# Sensore_esterno.net
KiCad netlist of a schematic drawn in EAGLE
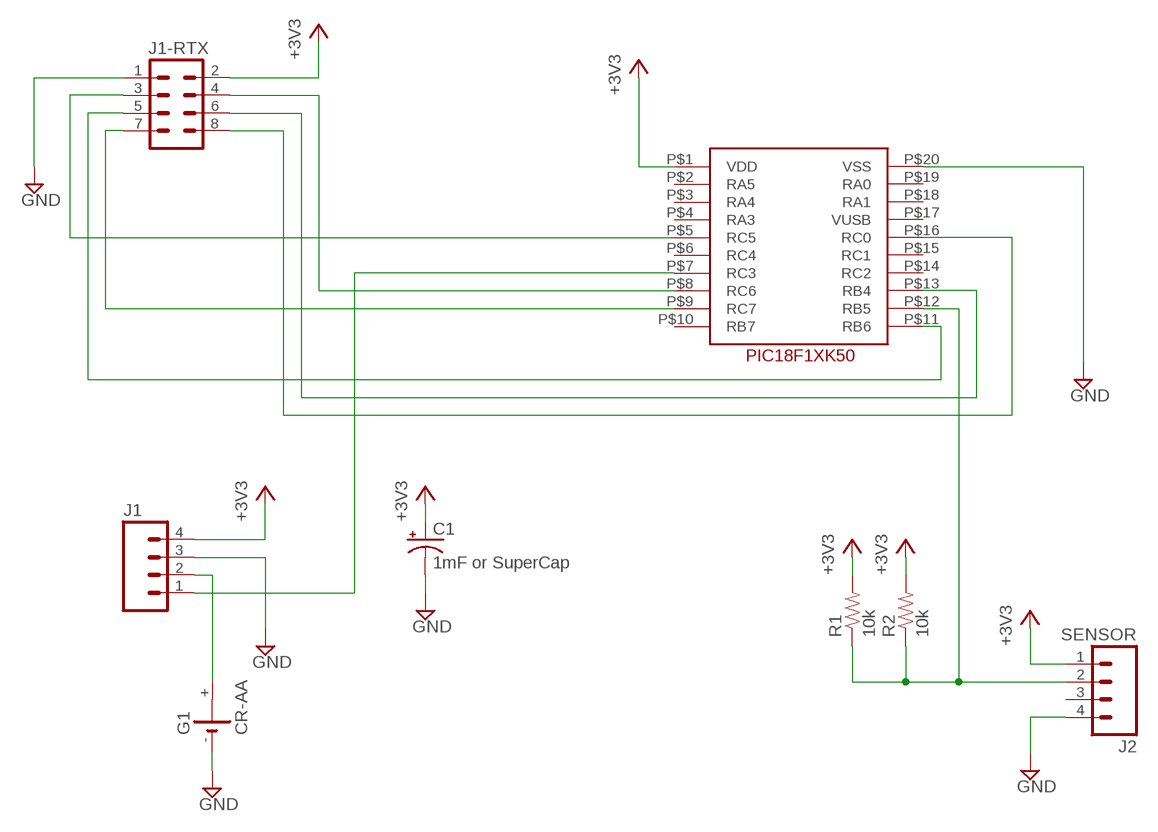
[diagram p0: schematic, sheet 1]

(export (version "E")
  (design (tool "Eeschema 10.0.6"))
  (components
    (comp (ref "C1")
      (value "1mF or SuperCap")
      (footprint "eagle-import:CPOL-RADIAL-1000UF-25V")
      (libsource (lib "eagle-import") (part "CAP_POLPTH4"))
    )
    (comp (ref "G1")
      (value "CR-AA")
      (footprint "eagle-import:CRAA")
      (libsource (lib "eagle-import") (part "CR-AA"))
    )
    (comp (ref "J1")
      (value "M04NO_SILK_ALL_ROUND")
      (footprint "eagle-import:1X04_NO_SILK_ALL_ROUND")
      (libsource (lib "eagle-import") (part "M04NO_SILK_ALL_ROUND"))
    )
    (comp (ref "J1-RTX")
      (value "M04X2")
      (footprint "eagle-import:2X4")
      (libsource (lib "eagle-import") (part "M04X2"))
    )
    (comp (ref "J2")
      (value "SENSOR")
      (footprint "eagle-import:1X04_NO_SILK_ALL_ROUND")
      (libsource (lib "eagle-import") (part "M04NO_SILK_ALL_ROUND"))
    )
    (comp (ref "R1")
      (value "10k")
      (footprint "eagle-import:AXIAL-0.3EZ")
      (libsource (lib "eagle-import") (part "RESISTOREZ"))
    )
    (comp (ref "R2")
      (value "10k")
      (footprint "eagle-import:AXIAL-0.3EZ")
      (libsource (lib "eagle-import") (part "RESISTOREZ"))
    )
    (comp (ref "U$1")
      (value "PIC18F1XK50")
      (footprint "eagle-import:SPDIP-20PIN")
      (libsource (lib "eagle-import") (part "PIC18F1XK50"))
    )
  )
  (nets
    (net (code "1") (name "+3V3") (class "Default")
      (node (ref "C1") (pin "1") (pinfunction "+_1") (pintype "passive"))
      (node (ref "J1") (pin "4") (pinfunction "4_4") (pintype "passive"))
      (node (ref "J1-RTX") (pin "2") (pinfunction "2_2") (pintype "passive"))
      (node (ref "J2") (pin "1") (pinfunction "1_1") (pintype "passive"))
      (node (ref "R1") (pin "P$2") (pinfunction "2_P$2") (pintype "passive"))
      (node (ref "R2") (pin "P$2") (pinfunction "2_P$2") (pintype "passive"))
      (node (ref "U$1") (pin "P$1") (pinfunction "VDD_P$1") (pintype "bidirectional"))
    )
    (net (code "2") (name "GND") (class "Default")
      (node (ref "C1") (pin "2") (pinfunction "-_2") (pintype "passive"))
      (node (ref "G1") (pin "-") (pinfunction "-_-") (pintype "passive"))
      (node (ref "J1") (pin "3") (pinfunction "3_3") (pintype "passive"))
      (node (ref "J1-RTX") (pin "1") (pinfunction "1_1") (pintype "passive"))
      (node (ref "J2") (pin "4") (pinfunction "4_4") (pintype "passive"))
      (node (ref "U$1") (pin "P$20") (pinfunction "VSS_P$20") (pintype "bidirectional"))
    )
    (net (code "3") (name "Net-(G1-Pad+)") (class "Default")
      (node (ref "G1") (pin "+") (pinfunction "+_+") (pintype "passive"))
      (node (ref "J1") (pin "2") (pinfunction "2_2") (pintype "passive"))
    )
    (net (code "4") (name "Net-(R1-1)") (class "Default")
      (node (ref "J2") (pin "2") (pinfunction "2_2") (pintype "passive"))
      (node (ref "R1") (pin "P$1") (pinfunction "1_P$1") (pintype "passive"))
      (node (ref "R2") (pin "P$1") (pinfunction "1_P$1") (pintype "passive"))
      (node (ref "U$1") (pin "P$12") (pinfunction "RB5_P$12") (pintype "bidirectional"))
    )
    (net (code "5") (name "Net-(U$1-RB4)") (class "Default")
      (node (ref "J1-RTX") (pin "6") (pinfunction "6_6") (pintype "passive"))
      (node (ref "U$1") (pin "P$13") (pinfunction "RB4_P$13") (pintype "bidirectional"))
    )
    (net (code "6") (name "Net-(U$1-RB6)") (class "Default")
      (node (ref "J1-RTX") (pin "5") (pinfunction "5_5") (pintype "passive"))
      (node (ref "U$1") (pin "P$11") (pinfunction "RB6_P$11") (pintype "bidirectional"))
    )
    (net (code "7") (name "Net-(U$1-RC0)") (class "Default")
      (node (ref "J1-RTX") (pin "8") (pinfunction "8_8") (pintype "passive"))
      (node (ref "U$1") (pin "P$16") (pinfunction "RC0_P$16") (pintype "bidirectional"))
    )
    (net (code "8") (name "Net-(U$1-RC3)") (class "Default")
      (node (ref "J1") (pin "1") (pinfunction "1_1") (pintype "passive"))
      (node (ref "U$1") (pin "P$7") (pinfunction "RC3_P$7") (pintype "bidirectional"))
    )
    (net (code "9") (name "Net-(U$1-RC5)") (class "Default")
      (node (ref "J1-RTX") (pin "3") (pinfunction "3_3") (pintype "passive"))
      (node (ref "U$1") (pin "P$5") (pinfunction "RC5_P$5") (pintype "bidirectional"))
    )
    (net (code "10") (name "Net-(U$1-RC6)") (class "Default")
      (node (ref "J1-RTX") (pin "4") (pinfunction "4_4") (pintype "passive"))
      (node (ref "U$1") (pin "P$8") (pinfunction "RC6_P$8") (pintype "bidirectional"))
    )
    (net (code "11") (name "Net-(U$1-RC7)") (class "Default")
      (node (ref "J1-RTX") (pin "7") (pinfunction "7_7") (pintype "passive"))
      (node (ref "U$1") (pin "P$9") (pinfunction "RC7_P$9") (pintype "bidirectional"))
    )
    (net (code "12") (name "unconnected-(G1-+-Pad+@1)") (class "Default")
      (node (ref "G1") (pin "+@1") (pinfunction "+_+@1") (pintype "passive"))
    )
    (net (code "13") (name "unconnected-(J2-Pad3)") (class "Default")
      (node (ref "J2") (pin "3") (pinfunction "3_3") (pintype "passive"))
    )
    (net (code "14") (name "unconnected-(U$1-RA0-PadP$19)") (class "Default")
      (node (ref "U$1") (pin "P$19") (pinfunction "RA0_P$19") (pintype "bidirectional"))
    )
    (net (code "15") (name "unconnected-(U$1-RA1-PadP$18)") (class "Default")
      (node (ref "U$1") (pin "P$18") (pinfunction "RA1_P$18") (pintype "bidirectional"))
    )
    (net (code "16") (name "unconnected-(U$1-RA3-PadP$4)") (class "Default")
      (node (ref "U$1") (pin "P$4") (pinfunction "RA3_P$4") (pintype "bidirectional"))
    )
    (net (code "17") (name "unconnected-(U$1-RA4-PadP$3)") (class "Default")
      (node (ref "U$1") (pin "P$3") (pinfunction "RA4_P$3") (pintype "bidirectional"))
    )
    (net (code "18") (name "unconnected-(U$1-RA5-PadP$2)") (class "Default")
      (node (ref "U$1") (pin "P$2") (pinfunction "RA5_P$2") (pintype "bidirectional"))
    )
    (net (code "19") (name "unconnected-(U$1-RB7-PadP$10)") (class "Default")
      (node (ref "U$1") (pin "P$10") (pinfunction "RB7_P$10") (pintype "bidirectional"))
    )
    (net (code "20") (name "unconnected-(U$1-RC1-PadP$15)") (class "Default")
      (node (ref "U$1") (pin "P$15") (pinfunction "RC1_P$15") (pintype "bidirectional"))
    )
    (net (code "21") (name "unconnected-(U$1-RC2-PadP$14)") (class "Default")
      (node (ref "U$1") (pin "P$14") (pinfunction "RC2_P$14") (pintype "bidirectional"))
    )
    (net (code "22") (name "unconnected-(U$1-RC4-PadP$6)") (class "Default")
      (node (ref "U$1") (pin "P$6") (pinfunction "RC4_P$6") (pintype "bidirectional"))
    )
    (net (code "23") (name "unconnected-(U$1-VUSB-PadP$17)") (class "Default")
      (node (ref "U$1") (pin "P$17") (pinfunction "VUSB_P$17") (pintype "bidirectional"))
    )
  )
)
